# MidiExpansion.net
KiCad netlist of a schematic drawn in EAGLE
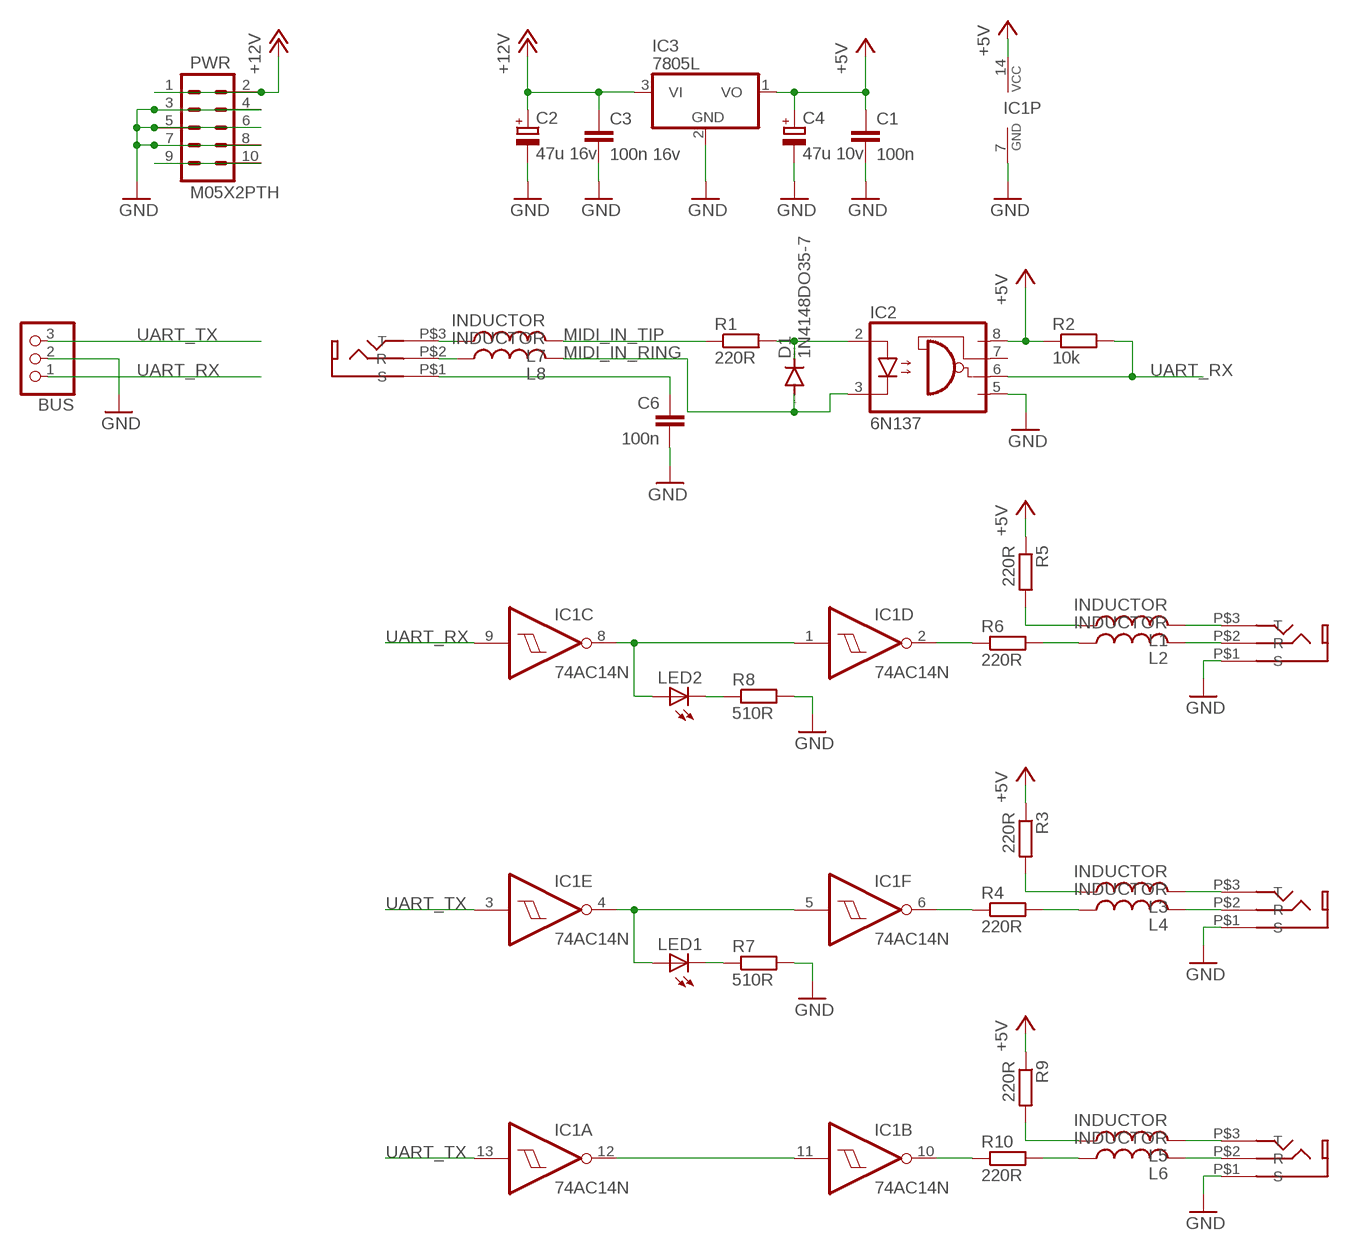
[diagram p0: schematic, sheet 1]

(export (version "E")
  (design (tool "Eeschema 10.0.6"))
  (components
    (comp (ref "BUS")
      (value "CON-JST-1X03PH-TH")
      (footprint "eagle-import:JST-B3B-PH-KL")
      (libsource (lib "eagle-import") (part "CON-JST-1X03PH-TH"))
    )
    (comp (ref "C1")
      (value "100n")
      (footprint "eagle-import:C050-024X044")
      (libsource (lib "eagle-import") (part "C-EU050-024X044"))
    )
    (comp (ref "C2")
      (value "47u 16v")
      (footprint "eagle-import:E5-6")
      (libsource (lib "eagle-import") (part "CPOL-EUE5-6"))
    )
    (comp (ref "C3")
      (value "100n 16v")
      (footprint "eagle-import:C050-024X044")
      (libsource (lib "eagle-import") (part "C-EU050-024X044"))
    )
    (comp (ref "C4")
      (value "47u 10v")
      (footprint "eagle-import:E5-6")
      (libsource (lib "eagle-import") (part "CPOL-EUE5-6"))
    )
    (comp (ref "C6")
      (value "100n")
      (footprint "eagle-import:C050-024X044")
      (libsource (lib "eagle-import") (part "C-EU050-024X044"))
    )
    (comp (ref "D1")
      (value "1N4148DO35-7")
      (footprint "eagle-import:DO35-7")
      (libsource (lib "eagle-import") (part "1N4148DO35-7"))
    )
    (comp (ref "IC1")
      (value "74AC14N")
      (footprint "eagle-import:DIL14")
      (libsource (lib "eagle-import") (part "7414NAC"))
    )
    (comp (ref "IC2")
      (value "6N137")
      (footprint "eagle-import:DIL08")
      (libsource (lib "eagle-import") (part "6N137"))
    )
    (comp (ref "IC3")
      (value "7805L")
      (footprint "eagle-import:TO92")
      (libsource (lib "eagle-import") (part "78L05"))
    )
    (comp (ref "L1")
      (value "INDUCTOR")
      (footprint "eagle-import:0603")
      (libsource (lib "eagle-import") (part "INDUCTOR"))
    )
    (comp (ref "L2")
      (value "INDUCTOR")
      (footprint "eagle-import:0603")
      (libsource (lib "eagle-import") (part "INDUCTOR"))
    )
    (comp (ref "L3")
      (value "INDUCTOR")
      (footprint "eagle-import:0603")
      (libsource (lib "eagle-import") (part "INDUCTOR"))
    )
    (comp (ref "L4")
      (value "INDUCTOR")
      (footprint "eagle-import:0603")
      (libsource (lib "eagle-import") (part "INDUCTOR"))
    )
    (comp (ref "L5")
      (value "INDUCTOR")
      (footprint "eagle-import:0603")
      (libsource (lib "eagle-import") (part "INDUCTOR"))
    )
    (comp (ref "L6")
      (value "INDUCTOR")
      (footprint "eagle-import:0603")
      (libsource (lib "eagle-import") (part "INDUCTOR"))
    )
    (comp (ref "L7")
      (value "INDUCTOR")
      (footprint "eagle-import:0603")
      (libsource (lib "eagle-import") (part "INDUCTOR"))
    )
    (comp (ref "L8")
      (value "INDUCTOR")
      (footprint "eagle-import:0603")
      (libsource (lib "eagle-import") (part "INDUCTOR"))
    )
    (comp (ref "LED1")
      (value "LED3MM")
      (footprint "eagle-import:LED3MM")
      (libsource (lib "eagle-import") (part "LED3MM"))
    )
    (comp (ref "LED2")
      (value "LED3MM")
      (footprint "eagle-import:LED3MM")
      (libsource (lib "eagle-import") (part "LED3MM"))
    )
    (comp (ref "MIDI_IN")
      (value "THONKICONN_STEREO")
      (footprint "eagle-import:THONKICONN_STEREO")
      (libsource (lib "eagle-import") (part "THONKICONN_STEREO"))
    )
    (comp (ref "MIDI_OUT")
      (value "THONKICONN_STEREO")
      (footprint "eagle-import:THONKICONN_STEREO")
      (libsource (lib "eagle-import") (part "THONKICONN_STEREO"))
    )
    (comp (ref "MIDI_OUT1")
      (value "THONKICONN_STEREO")
      (footprint "eagle-import:THONKICONN_STEREO")
      (libsource (lib "eagle-import") (part "THONKICONN_STEREO"))
    )
    (comp (ref "MIDI_THRU")
      (value "THONKICONN_STEREO")
      (footprint "eagle-import:THONKICONN_STEREO")
      (libsource (lib "eagle-import") (part "THONKICONN_STEREO"))
    )
    (comp (ref "PWR")
      (value "M05X2PTH")
      (footprint "eagle-import:AVR_ICSP")
      (libsource (lib "eagle-import") (part "M05X2PTH"))
    )
    (comp (ref "R1")
      (value "220R")
      (footprint "eagle-import:0204_7")
      (libsource (lib "eagle-import") (part "R-EU_0204/7"))
    )
    (comp (ref "R2")
      (value "10k")
      (footprint "eagle-import:0204_7")
      (libsource (lib "eagle-import") (part "R-EU_0204/7"))
    )
    (comp (ref "R3")
      (value "220R")
      (footprint "eagle-import:0204_7")
      (libsource (lib "eagle-import") (part "R-EU_0204/7"))
    )
    (comp (ref "R4")
      (value "220R")
      (footprint "eagle-import:0204_7")
      (libsource (lib "eagle-import") (part "R-EU_0204/7"))
    )
    (comp (ref "R5")
      (value "220R")
      (footprint "eagle-import:0204_7")
      (libsource (lib "eagle-import") (part "R-EU_0204/7"))
    )
    (comp (ref "R6")
      (value "220R")
      (footprint "eagle-import:0204_7")
      (libsource (lib "eagle-import") (part "R-EU_0204/7"))
    )
    (comp (ref "R7")
      (value "510R")
      (footprint "eagle-import:0204_7")
      (libsource (lib "eagle-import") (part "R-EU_0204/7"))
    )
    (comp (ref "R8")
      (value "510R")
      (footprint "eagle-import:0204_7")
      (libsource (lib "eagle-import") (part "R-EU_0204/7"))
    )
    (comp (ref "R9")
      (value "220R")
      (footprint "eagle-import:0204_7")
      (libsource (lib "eagle-import") (part "R-EU_0204/7"))
    )
    (comp (ref "R10")
      (value "220R")
      (footprint "eagle-import:0204_7")
      (libsource (lib "eagle-import") (part "R-EU_0204/7"))
    )
  )
  (nets
    (net (code "1") (name "+5V") (class "Default")
      (node (ref "C1") (pin "1") (pinfunction "1_1") (pintype "passive"))
      (node (ref "C4") (pin "+") (pinfunction "+_+") (pintype "passive"))
      (node (ref "IC1") (pin "14") (pinfunction "VCC_14") (pintype "power_in"))
      (node (ref "IC2") (pin "8") (pinfunction "VCC_8") (pintype "passive"))
      (node (ref "IC3") (pin "1") (pinfunction "VO_1") (pintype "passive"))
      (node (ref "R2") (pin "1") (pinfunction "1_1") (pintype "passive"))
      (node (ref "R3") (pin "1") (pinfunction "1_1") (pintype "passive"))
      (node (ref "R5") (pin "1") (pinfunction "1_1") (pintype "passive"))
      (node (ref "R9") (pin "1") (pinfunction "1_1") (pintype "passive"))
    )
    (net (code "2") (name "+12V") (class "Default")
      (node (ref "C2") (pin "+") (pinfunction "+_+") (pintype "passive"))
      (node (ref "C3") (pin "1") (pinfunction "1_1") (pintype "passive"))
      (node (ref "IC3") (pin "3") (pinfunction "VI_3") (pintype "input"))
      (node (ref "PWR") (pin "1") (pinfunction "1_1") (pintype "passive"))
      (node (ref "PWR") (pin "2") (pinfunction "2_2") (pintype "passive"))
    )
    (net (code "3") (name "/MIDI_IN_RING") (class "Default")
      (node (ref "D1") (pin "A") (pinfunction "A_A") (pintype "passive"))
      (node (ref "IC2") (pin "3") (pinfunction "C_3") (pintype "passive"))
      (node (ref "L8") (pin "2") (pinfunction "2_2") (pintype "passive"))
    )
    (net (code "4") (name "/MIDI_IN_TIP") (class "Default")
      (node (ref "L7") (pin "2") (pinfunction "2_2") (pintype "passive"))
      (node (ref "R1") (pin "1") (pinfunction "1_1") (pintype "passive"))
    )
    (net (code "5") (name "/UART_RX") (class "Default")
      (node (ref "BUS") (pin "1") (pinfunction "1_1") (pintype "passive"))
      (node (ref "IC1") (pin "9") (pinfunction "I_9") (pintype "input"))
      (node (ref "IC2") (pin "6") (pinfunction "VO_6") (pintype "passive"))
      (node (ref "R2") (pin "2") (pinfunction "2_2") (pintype "passive"))
    )
    (net (code "6") (name "/UART_TX") (class "Default")
      (node (ref "BUS") (pin "3") (pinfunction "3_3") (pintype "passive"))
      (node (ref "IC1") (pin "13") (pinfunction "I_13") (pintype "input"))
      (node (ref "IC1") (pin "3") (pinfunction "I_3") (pintype "input"))
    )
    (net (code "7") (name "GND") (class "Default")
      (node (ref "BUS") (pin "2") (pinfunction "2_2") (pintype "passive"))
      (node (ref "C1") (pin "2") (pinfunction "2_2") (pintype "passive"))
      (node (ref "C2") (pin "-") (pinfunction "-_-") (pintype "passive"))
      (node (ref "C3") (pin "2") (pinfunction "2_2") (pintype "passive"))
      (node (ref "C4") (pin "-") (pinfunction "-_-") (pintype "passive"))
      (node (ref "C6") (pin "2") (pinfunction "2_2") (pintype "passive"))
      (node (ref "IC1") (pin "7") (pinfunction "GND_7") (pintype "power_in"))
      (node (ref "IC2") (pin "5") (pinfunction "GND_5") (pintype "passive"))
      (node (ref "IC3") (pin "2") (pinfunction "GND_2") (pintype "passive"))
      (node (ref "MIDI_OUT") (pin "P$1") (pinfunction "S_P$1") (pintype "bidirectional"))
      (node (ref "MIDI_OUT1") (pin "P$1") (pinfunction "S_P$1") (pintype "bidirectional"))
      (node (ref "MIDI_THRU") (pin "P$1") (pinfunction "S_P$1") (pintype "bidirectional"))
      (node (ref "PWR") (pin "3") (pinfunction "3_3") (pintype "passive"))
      (node (ref "PWR") (pin "4") (pinfunction "4_4") (pintype "passive"))
      (node (ref "PWR") (pin "5") (pinfunction "5_5") (pintype "passive"))
      (node (ref "PWR") (pin "6") (pinfunction "6_6") (pintype "passive"))
      (node (ref "PWR") (pin "7") (pinfunction "7_7") (pintype "passive"))
      (node (ref "PWR") (pin "8") (pinfunction "8_8") (pintype "passive"))
      (node (ref "R7") (pin "2") (pinfunction "2_2") (pintype "passive"))
      (node (ref "R8") (pin "2") (pinfunction "2_2") (pintype "passive"))
    )
    (net (code "8") (name "Net-(IC1A-O)") (class "Default")
      (node (ref "IC1") (pin "11") (pinfunction "I_11") (pintype "input"))
      (node (ref "IC1") (pin "12") (pinfunction "O_12") (pintype "output"))
    )
    (net (code "9") (name "Net-(IC1B-O)") (class "Default")
      (node (ref "IC1") (pin "10") (pinfunction "O_10") (pintype "output"))
      (node (ref "R10") (pin "1") (pinfunction "1_1") (pintype "passive"))
    )
    (net (code "10") (name "Net-(IC1C-O)") (class "Default")
      (node (ref "IC1") (pin "1") (pinfunction "I_1") (pintype "input"))
      (node (ref "IC1") (pin "8") (pinfunction "O_8") (pintype "output"))
      (node (ref "LED2") (pin "A") (pinfunction "A_A") (pintype "passive"))
    )
    (net (code "11") (name "Net-(IC1D-O)") (class "Default")
      (node (ref "IC1") (pin "2") (pinfunction "O_2") (pintype "output"))
      (node (ref "R6") (pin "1") (pinfunction "1_1") (pintype "passive"))
    )
    (net (code "12") (name "Net-(IC1E-O)") (class "Default")
      (node (ref "IC1") (pin "4") (pinfunction "O_4") (pintype "output"))
      (node (ref "IC1") (pin "5") (pinfunction "I_5") (pintype "input"))
      (node (ref "LED1") (pin "A") (pinfunction "A_A") (pintype "passive"))
    )
    (net (code "13") (name "Net-(IC1F-O)") (class "Default")
      (node (ref "IC1") (pin "6") (pinfunction "O_6") (pintype "output"))
      (node (ref "R4") (pin "1") (pinfunction "1_1") (pintype "passive"))
    )
    (net (code "14") (name "Net-(IC2-A)") (class "Default")
      (node (ref "D1") (pin "C") (pinfunction "C_C") (pintype "passive"))
      (node (ref "IC2") (pin "2") (pinfunction "A_2") (pintype "passive"))
      (node (ref "R1") (pin "2") (pinfunction "2_2") (pintype "passive"))
    )
    (net (code "15") (name "Net-(L1-Pad1)") (class "Default")
      (node (ref "L1") (pin "1") (pinfunction "1_1") (pintype "passive"))
      (node (ref "R5") (pin "2") (pinfunction "2_2") (pintype "passive"))
    )
    (net (code "16") (name "Net-(L2-Pad1)") (class "Default")
      (node (ref "L2") (pin "1") (pinfunction "1_1") (pintype "passive"))
      (node (ref "R6") (pin "2") (pinfunction "2_2") (pintype "passive"))
    )
    (net (code "17") (name "Net-(L3-Pad1)") (class "Default")
      (node (ref "L3") (pin "1") (pinfunction "1_1") (pintype "passive"))
      (node (ref "R3") (pin "2") (pinfunction "2_2") (pintype "passive"))
    )
    (net (code "18") (name "Net-(L4-Pad1)") (class "Default")
      (node (ref "L4") (pin "1") (pinfunction "1_1") (pintype "passive"))
      (node (ref "R4") (pin "2") (pinfunction "2_2") (pintype "passive"))
    )
    (net (code "19") (name "Net-(L5-Pad1)") (class "Default")
      (node (ref "L5") (pin "1") (pinfunction "1_1") (pintype "passive"))
      (node (ref "R9") (pin "2") (pinfunction "2_2") (pintype "passive"))
    )
    (net (code "20") (name "Net-(L6-Pad1)") (class "Default")
      (node (ref "L6") (pin "1") (pinfunction "1_1") (pintype "passive"))
      (node (ref "R10") (pin "2") (pinfunction "2_2") (pintype "passive"))
    )
    (net (code "21") (name "Net-(LED1-C)") (class "Default")
      (node (ref "LED1") (pin "K") (pinfunction "C_K") (pintype "passive"))
      (node (ref "R7") (pin "1") (pinfunction "1_1") (pintype "passive"))
    )
    (net (code "22") (name "Net-(LED2-C)") (class "Default")
      (node (ref "LED2") (pin "K") (pinfunction "C_K") (pintype "passive"))
      (node (ref "R8") (pin "1") (pinfunction "1_1") (pintype "passive"))
    )
    (net (code "23") (name "Net-(MIDI_IN-R)") (class "Default")
      (node (ref "L8") (pin "1") (pinfunction "1_1") (pintype "passive"))
      (node (ref "MIDI_IN") (pin "P$2") (pinfunction "R_P$2") (pintype "bidirectional"))
    )
    (net (code "24") (name "Net-(MIDI_IN-S)") (class "Default")
      (node (ref "C6") (pin "1") (pinfunction "1_1") (pintype "passive"))
      (node (ref "MIDI_IN") (pin "P$1") (pinfunction "S_P$1") (pintype "bidirectional"))
    )
    (net (code "25") (name "Net-(MIDI_IN-T)") (class "Default")
      (node (ref "L7") (pin "1") (pinfunction "1_1") (pintype "passive"))
      (node (ref "MIDI_IN") (pin "P$3") (pinfunction "T_P$3") (pintype "bidirectional"))
    )
    (net (code "26") (name "Net-(MIDI_OUT-R)") (class "Default")
      (node (ref "L4") (pin "2") (pinfunction "2_2") (pintype "passive"))
      (node (ref "MIDI_OUT") (pin "P$2") (pinfunction "R_P$2") (pintype "bidirectional"))
    )
    (net (code "27") (name "Net-(MIDI_OUT-T)") (class "Default")
      (node (ref "L3") (pin "2") (pinfunction "2_2") (pintype "passive"))
      (node (ref "MIDI_OUT") (pin "P$3") (pinfunction "T_P$3") (pintype "bidirectional"))
    )
    (net (code "28") (name "Net-(MIDI_OUT1-R)") (class "Default")
      (node (ref "L6") (pin "2") (pinfunction "2_2") (pintype "passive"))
      (node (ref "MIDI_OUT1") (pin "P$2") (pinfunction "R_P$2") (pintype "bidirectional"))
    )
    (net (code "29") (name "Net-(MIDI_OUT1-T)") (class "Default")
      (node (ref "L5") (pin "2") (pinfunction "2_2") (pintype "passive"))
      (node (ref "MIDI_OUT1") (pin "P$3") (pinfunction "T_P$3") (pintype "bidirectional"))
    )
    (net (code "30") (name "Net-(MIDI_THRU-R)") (class "Default")
      (node (ref "L2") (pin "2") (pinfunction "2_2") (pintype "passive"))
      (node (ref "MIDI_THRU") (pin "P$2") (pinfunction "R_P$2") (pintype "bidirectional"))
    )
    (net (code "31") (name "Net-(MIDI_THRU-T)") (class "Default")
      (node (ref "L1") (pin "2") (pinfunction "2_2") (pintype "passive"))
      (node (ref "MIDI_THRU") (pin "P$3") (pinfunction "T_P$3") (pintype "bidirectional"))
    )
    (net (code "32") (name "Net-(PWR-Pad10)") (class "Default")
      (node (ref "PWR") (pin "10") (pinfunction "10_10") (pintype "passive"))
      (node (ref "PWR") (pin "9") (pinfunction "9_9") (pintype "passive"))
    )
    (net (code "33") (name "unconnected-(IC2-VE-Pad7)") (class "Default")
      (node (ref "IC2") (pin "7") (pinfunction "VE_7") (pintype "passive"))
    )
  )
)
